# 4051-analogswitch.net
KiCad netlist of a schematic drawn in EAGLE
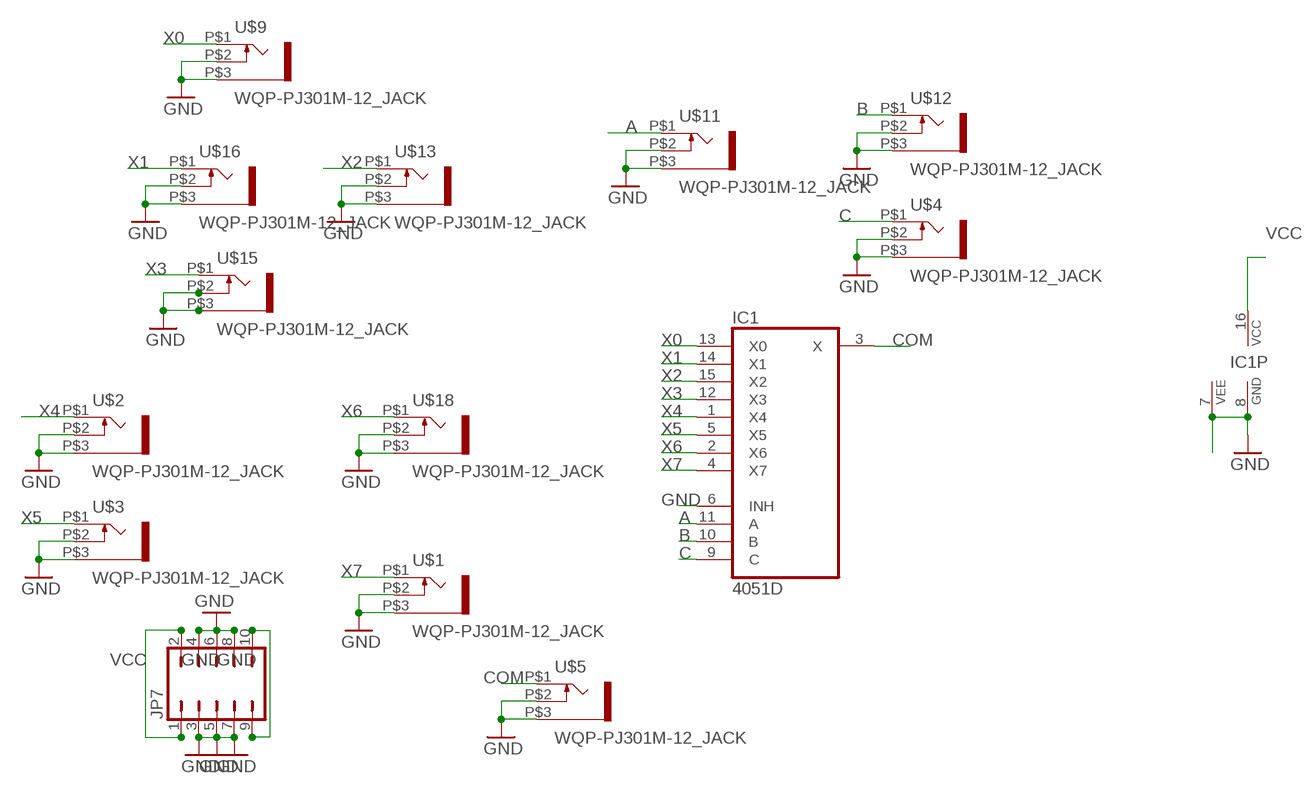
[diagram p0: schematic, sheet 1]

(export (version "E")
  (design (tool "Eeschema 10.0.6"))
  (components
    (comp (ref "IC1")
      (value "4051D")
      (footprint "eagle-import:SO16")
      (libsource (lib "eagle-import") (part "4051D"))
    )
    (comp (ref "JP7")
      (value "JP5Q")
      (footprint "eagle-import:JP5Q")
      (libsource (lib "eagle-import") (part "JP5Q"))
    )
    (comp (ref "U$1")
      (value "WQP-PJ301M-12_JACK")
      (footprint "eagle-import:WQP-PJ301M-12_JACK")
      (libsource (lib "eagle-import") (part "WQP-PJ301M-12_JACK"))
    )
    (comp (ref "U$2")
      (value "WQP-PJ301M-12_JACK")
      (footprint "eagle-import:WQP-PJ301M-12_JACK")
      (libsource (lib "eagle-import") (part "WQP-PJ301M-12_JACK"))
    )
    (comp (ref "U$3")
      (value "WQP-PJ301M-12_JACK")
      (footprint "eagle-import:WQP-PJ301M-12_JACK")
      (libsource (lib "eagle-import") (part "WQP-PJ301M-12_JACK"))
    )
    (comp (ref "U$4")
      (value "WQP-PJ301M-12_JACK")
      (footprint "eagle-import:WQP-PJ301M-12_JACK")
      (libsource (lib "eagle-import") (part "WQP-PJ301M-12_JACK"))
    )
    (comp (ref "U$5")
      (value "WQP-PJ301M-12_JACK")
      (footprint "eagle-import:WQP-PJ301M-12_JACK")
      (libsource (lib "eagle-import") (part "WQP-PJ301M-12_JACK"))
    )
    (comp (ref "U$9")
      (value "WQP-PJ301M-12_JACK")
      (footprint "eagle-import:WQP-PJ301M-12_JACK")
      (libsource (lib "eagle-import") (part "WQP-PJ301M-12_JACK"))
    )
    (comp (ref "U$11")
      (value "WQP-PJ301M-12_JACK")
      (footprint "eagle-import:WQP-PJ301M-12_JACK")
      (libsource (lib "eagle-import") (part "WQP-PJ301M-12_JACK"))
    )
    (comp (ref "U$12")
      (value "WQP-PJ301M-12_JACK")
      (footprint "eagle-import:WQP-PJ301M-12_JACK")
      (libsource (lib "eagle-import") (part "WQP-PJ301M-12_JACK"))
    )
    (comp (ref "U$13")
      (value "WQP-PJ301M-12_JACK")
      (footprint "eagle-import:WQP-PJ301M-12_JACK")
      (libsource (lib "eagle-import") (part "WQP-PJ301M-12_JACK"))
    )
    (comp (ref "U$15")
      (value "WQP-PJ301M-12_JACK")
      (footprint "eagle-import:WQP-PJ301M-12_JACK")
      (libsource (lib "eagle-import") (part "WQP-PJ301M-12_JACK"))
    )
    (comp (ref "U$16")
      (value "WQP-PJ301M-12_JACK")
      (footprint "eagle-import:WQP-PJ301M-12_JACK")
      (libsource (lib "eagle-import") (part "WQP-PJ301M-12_JACK"))
    )
    (comp (ref "U$18")
      (value "WQP-PJ301M-12_JACK")
      (footprint "eagle-import:WQP-PJ301M-12_JACK")
      (libsource (lib "eagle-import") (part "WQP-PJ301M-12_JACK"))
    )
  )
  (nets
    (net (code "1") (name "/A") (class "Default")
      (node (ref "IC1") (pin "11") (pinfunction "A_11") (pintype "input"))
      (node (ref "U$11") (pin "P$1") (pinfunction "2_P$1") (pintype "passive"))
    )
    (net (code "2") (name "/B") (class "Default")
      (node (ref "IC1") (pin "10") (pinfunction "B_10") (pintype "input"))
      (node (ref "U$12") (pin "P$1") (pinfunction "2_P$1") (pintype "passive"))
    )
    (net (code "3") (name "/C") (class "Default")
      (node (ref "IC1") (pin "9") (pinfunction "C_9") (pintype "input"))
      (node (ref "U$4") (pin "P$1") (pinfunction "2_P$1") (pintype "passive"))
    )
    (net (code "4") (name "/COM") (class "Default")
      (node (ref "IC1") (pin "3") (pinfunction "X_3") (pintype "bidirectional"))
      (node (ref "U$5") (pin "P$1") (pinfunction "2_P$1") (pintype "passive"))
    )
    (net (code "5") (name "/VCC") (class "Default")
      (node (ref "IC1") (pin "16") (pinfunction "VCC_16") (pintype "power_in"))
      (node (ref "JP7") (pin "1") (pinfunction "1_1") (pintype "passive"))
      (node (ref "JP7") (pin "2") (pinfunction "2_2") (pintype "passive"))
    )
    (net (code "6") (name "/X0") (class "Default")
      (node (ref "IC1") (pin "13") (pinfunction "X0_13") (pintype "bidirectional"))
      (node (ref "U$9") (pin "P$1") (pinfunction "2_P$1") (pintype "passive"))
    )
    (net (code "7") (name "/X1") (class "Default")
      (node (ref "IC1") (pin "14") (pinfunction "X1_14") (pintype "bidirectional"))
      (node (ref "U$16") (pin "P$1") (pinfunction "2_P$1") (pintype "passive"))
    )
    (net (code "8") (name "/X2") (class "Default")
      (node (ref "IC1") (pin "15") (pinfunction "X2_15") (pintype "bidirectional"))
      (node (ref "U$13") (pin "P$1") (pinfunction "2_P$1") (pintype "passive"))
    )
    (net (code "9") (name "/X3") (class "Default")
      (node (ref "IC1") (pin "12") (pinfunction "X3_12") (pintype "bidirectional"))
      (node (ref "U$15") (pin "P$1") (pinfunction "2_P$1") (pintype "passive"))
    )
    (net (code "10") (name "/X4") (class "Default")
      (node (ref "IC1") (pin "1") (pinfunction "X4_1") (pintype "bidirectional"))
      (node (ref "U$2") (pin "P$1") (pinfunction "2_P$1") (pintype "passive"))
    )
    (net (code "11") (name "/X5") (class "Default")
      (node (ref "IC1") (pin "5") (pinfunction "X5_5") (pintype "bidirectional"))
      (node (ref "U$3") (pin "P$1") (pinfunction "2_P$1") (pintype "passive"))
    )
    (net (code "12") (name "/X6") (class "Default")
      (node (ref "IC1") (pin "2") (pinfunction "X6_2") (pintype "bidirectional"))
      (node (ref "U$18") (pin "P$1") (pinfunction "2_P$1") (pintype "passive"))
    )
    (net (code "13") (name "/X7") (class "Default")
      (node (ref "IC1") (pin "4") (pinfunction "X7_4") (pintype "bidirectional"))
      (node (ref "U$1") (pin "P$1") (pinfunction "2_P$1") (pintype "passive"))
    )
    (net (code "14") (name "GND") (class "Default")
      (node (ref "IC1") (pin "6") (pinfunction "INH_6") (pintype "input"))
      (node (ref "IC1") (pin "7") (pinfunction "VEE_7") (pintype "power_in"))
      (node (ref "IC1") (pin "8") (pinfunction "GND_8") (pintype "power_in"))
      (node (ref "JP7") (pin "3") (pinfunction "3_3") (pintype "passive"))
      (node (ref "JP7") (pin "4") (pinfunction "4_4") (pintype "passive"))
      (node (ref "JP7") (pin "5") (pinfunction "5_5") (pintype "passive"))
      (node (ref "JP7") (pin "6") (pinfunction "6_6") (pintype "passive"))
      (node (ref "JP7") (pin "7") (pinfunction "7_7") (pintype "passive"))
      (node (ref "JP7") (pin "8") (pinfunction "8_8") (pintype "passive"))
      (node (ref "U$1") (pin "P$2") (pinfunction "3_P$2") (pintype "passive"))
      (node (ref "U$1") (pin "P$3") (pinfunction "1_P$3") (pintype "passive"))
      (node (ref "U$11") (pin "P$2") (pinfunction "3_P$2") (pintype "passive"))
      (node (ref "U$11") (pin "P$3") (pinfunction "1_P$3") (pintype "passive"))
      (node (ref "U$12") (pin "P$2") (pinfunction "3_P$2") (pintype "passive"))
      (node (ref "U$12") (pin "P$3") (pinfunction "1_P$3") (pintype "passive"))
      (node (ref "U$13") (pin "P$2") (pinfunction "3_P$2") (pintype "passive"))
      (node (ref "U$13") (pin "P$3") (pinfunction "1_P$3") (pintype "passive"))
      (node (ref "U$15") (pin "P$2") (pinfunction "3_P$2") (pintype "passive"))
      (node (ref "U$15") (pin "P$3") (pinfunction "1_P$3") (pintype "passive"))
      (node (ref "U$16") (pin "P$2") (pinfunction "3_P$2") (pintype "passive"))
      (node (ref "U$16") (pin "P$3") (pinfunction "1_P$3") (pintype "passive"))
      (node (ref "U$18") (pin "P$2") (pinfunction "3_P$2") (pintype "passive"))
      (node (ref "U$18") (pin "P$3") (pinfunction "1_P$3") (pintype "passive"))
      (node (ref "U$2") (pin "P$2") (pinfunction "3_P$2") (pintype "passive"))
      (node (ref "U$2") (pin "P$3") (pinfunction "1_P$3") (pintype "passive"))
      (node (ref "U$3") (pin "P$2") (pinfunction "3_P$2") (pintype "passive"))
      (node (ref "U$3") (pin "P$3") (pinfunction "1_P$3") (pintype "passive"))
      (node (ref "U$4") (pin "P$2") (pinfunction "3_P$2") (pintype "passive"))
      (node (ref "U$4") (pin "P$3") (pinfunction "1_P$3") (pintype "passive"))
      (node (ref "U$5") (pin "P$2") (pinfunction "3_P$2") (pintype "passive"))
      (node (ref "U$5") (pin "P$3") (pinfunction "1_P$3") (pintype "passive"))
      (node (ref "U$9") (pin "P$2") (pinfunction "3_P$2") (pintype "passive"))
      (node (ref "U$9") (pin "P$3") (pinfunction "1_P$3") (pintype "passive"))
    )
    (net (code "15") (name "Net-(JP7-Pad10)") (class "Default")
      (node (ref "JP7") (pin "10") (pinfunction "10_10") (pintype "passive"))
      (node (ref "JP7") (pin "9") (pinfunction "9_9") (pintype "passive"))
    )
  )
)
